# 2_5V_REF.net
KiCad netlist of a schematic drawn in Altium Designer
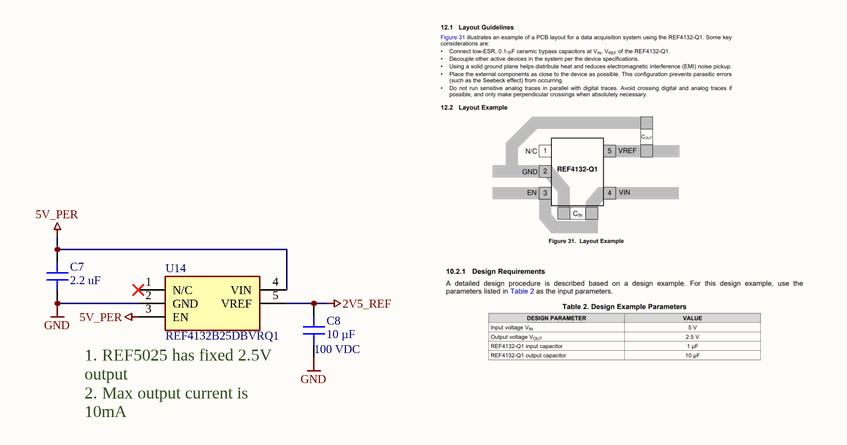
[diagram p0: 2.5V_REF.SchDoc]

(export (version "E")
  (design (tool "Eeschema 10.0.6"))
  (components
    (comp (ref "C7")
      (value "2.2 uF")
      (footprint "C_0603")
      (description "Capacitor 0603, 25 VDC, 2.2 uF, X5R")
      (fields
        (field (name "MANUFACTURER PART NUMBER") "C1608X5R1E225K080AB")
        (field (name "MANUFACTURER") "TDK")
        (field (name "CREATED FROM") "DHufnagel")
      )
      (libsource (lib "user") (part "Capacitor"))
    )
    (comp (ref "C8")
      (value "10 µF")
      (footprint "C_1210_N")
      (description "Capacitor 1210, 100 VDC, 10µF, X7S")
      (fields
        (field (name "MANUFACTURER PART NUMBER") "GRM32EC72A106KE05L")
        (field (name "MANUFACTURER") "Murata Electronics")
        (field (name "VOLTAGE RATING") "100 VDC")
        (field (name "CREATED FROM") "DHufnagel")
      )
      (libsource (lib "user") (part "Capacitor"))
    )
    (comp (ref "U14")
      (value "REF4132B25DBVRQ1")
      (footprint "SOT95P280X145-5N")
      (description "Voltage Reference, 2.5V, ±0.05%, ±10mA")
      (fields (field (name "MANUFACTURER") "Texas Instruments") (field (name "CREATED FROM") "DHufnagel"))
      (libsource (lib "user") (part "REF4132B25DBVRQ1"))
    )
  )
  (nets
    (net (code "1") (name "2V5_REF") (class "Default")
      (node (ref "C8") (pin "2") (pinfunction "2_2") (pintype "passive"))
      (node (ref "U14") (pin "5") (pinfunction "VREF_5") (pintype "passive"))
    )
    (net (code "2") (name "5V_PER") (class "Default")
      (node (ref "C7") (pin "2") (pinfunction "2_2") (pintype "passive"))
      (node (ref "U14") (pin "3") (pinfunction "EN_3") (pintype "passive"))
      (node (ref "U14") (pin "4") (pinfunction "VIN_4") (pintype "passive"))
    )
    (net (code "3") (name "GND") (class "Default")
      (node (ref "C7") (pin "1") (pinfunction "1_1") (pintype "passive"))
      (node (ref "C8") (pin "1") (pinfunction "1_1") (pintype "passive"))
      (node (ref "U14") (pin "2") (pinfunction "GND_2") (pintype "passive"))
    )
    (net (code "4") (name "unconnected-(U14-N{slash}C-Pad1)") (class "Default")
      (node (ref "U14") (pin "1") (pinfunction "N/C_1") (pintype "passive+no_connect"))
    )
  )
)
